# mfl_modul_u6052b.net
KiCad netlist of a schematic drawn in EAGLE
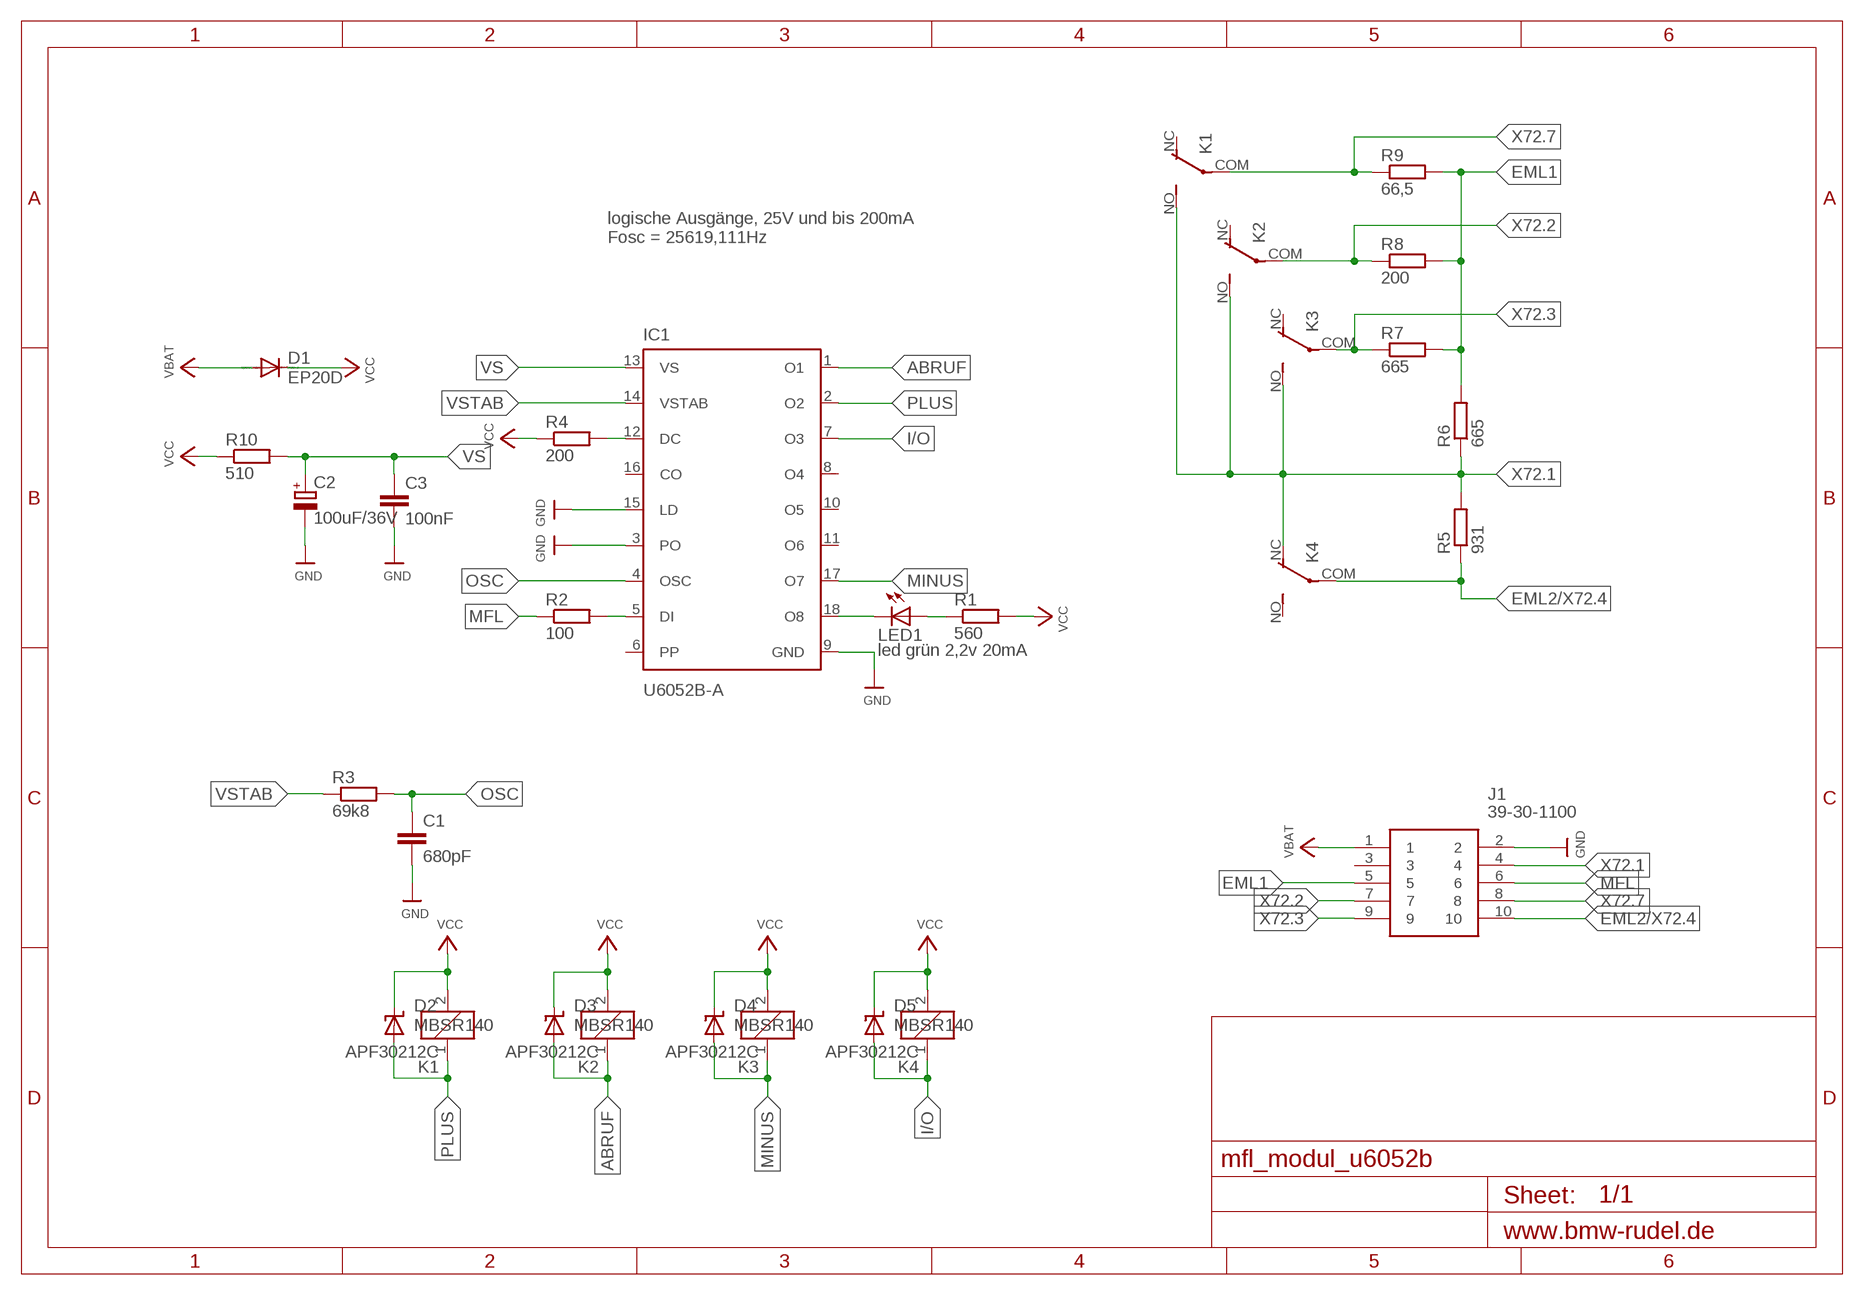
[diagram p0: schematic, sheet 1]

(export (version "E")
  (design (tool "Eeschema 10.0.6"))
  (components
    (comp (ref "C1")
      (value "680pF")
      (footprint "eagle-import:C025-025X050")
      (libsource (lib "eagle-import") (part "C-EU025-025X050"))
    )
    (comp (ref "C2")
      (value "100uF/36V")
      (footprint "eagle-import:E2,5-6")
      (libsource (lib "eagle-import") (part "CPOL-EUE2.5-6"))
    )
    (comp (ref "C3")
      (value "100nF")
      (footprint "eagle-import:C025-025X050")
      (libsource (lib "eagle-import") (part "C-EU025-025X050"))
    )
    (comp (ref "D1")
      (value "EP20D")
      (footprint "eagle-import:DO15-12")
      (libsource (lib "eagle-import") (part "DIODE-DO15-12"))
    )
    (comp (ref "D2")
      (value "MBSR140")
      (footprint "eagle-import:DO214AA")
      (libsource (lib "eagle-import") (part "SHOTKY-SMDSMB"))
    )
    (comp (ref "D3")
      (value "MBSR140")
      (footprint "eagle-import:DO214AA")
      (libsource (lib "eagle-import") (part "SHOTKY-SMDSMB"))
    )
    (comp (ref "D4")
      (value "MBSR140")
      (footprint "eagle-import:DO214AA")
      (libsource (lib "eagle-import") (part "SHOTKY-SMDSMB"))
    )
    (comp (ref "D5")
      (value "MBSR140")
      (footprint "eagle-import:DO214AA")
      (libsource (lib "eagle-import") (part "SHOTKY-SMDSMB"))
    )
    (comp (ref "IC1")
      (value "U6052B-A")
      (footprint "eagle-import:DIL18")
      (libsource (lib "eagle-import") (part "U6052B-A"))
    )
    (comp (ref "J1")
      (value "39-30-1100")
      (footprint "eagle-import:39-30-1100")
      (fields (field (name "MOUSER_PART_NUMBER") "538-39-30-1100") (field (name "RS_PART_NUMBER") "5109871P"))
      (libsource (lib "eagle-import") (part "39-30-1100"))
    )
    (comp (ref "K1")
      (value "APF30212C")
      (footprint "eagle-import:APF30212C")
      (libsource (lib "eagle-import") (part "APF30212C"))
    )
    (comp (ref "K2")
      (value "APF30212C")
      (footprint "eagle-import:APF30212C")
      (libsource (lib "eagle-import") (part "APF30212C"))
    )
    (comp (ref "K3")
      (value "APF30212C")
      (footprint "eagle-import:APF30212C")
      (libsource (lib "eagle-import") (part "APF30212C"))
    )
    (comp (ref "K4")
      (value "APF30212C")
      (footprint "eagle-import:APF30212C")
      (libsource (lib "eagle-import") (part "APF30212C"))
    )
    (comp (ref "LED1")
      (value "led grün 2,2v 20mA")
      (footprint "eagle-import:LED3MM")
      (libsource (lib "eagle-import") (part "LED3MM"))
    )
    (comp (ref "R1")
      (value "560")
      (footprint "eagle-import:0207_7")
      (libsource (lib "eagle-import") (part "R-EU_0207/7"))
    )
    (comp (ref "R2")
      (value "100")
      (footprint "eagle-import:0207_7")
      (libsource (lib "eagle-import") (part "R-EU_0207/7"))
    )
    (comp (ref "R3")
      (value "69k8")
      (footprint "eagle-import:0207_7")
      (libsource (lib "eagle-import") (part "R-EU_0207/7"))
    )
    (comp (ref "R4")
      (value "200")
      (footprint "eagle-import:0207_7")
      (libsource (lib "eagle-import") (part "R-EU_0207/7"))
    )
    (comp (ref "R5")
      (value "931")
      (footprint "eagle-import:0207_7")
      (libsource (lib "eagle-import") (part "R-EU_0207/7"))
    )
    (comp (ref "R6")
      (value "665")
      (footprint "eagle-import:0207_7")
      (libsource (lib "eagle-import") (part "R-EU_0207/7"))
    )
    (comp (ref "R7")
      (value "665")
      (footprint "eagle-import:0207_7")
      (libsource (lib "eagle-import") (part "R-EU_0207/7"))
    )
    (comp (ref "R8")
      (value "200")
      (footprint "eagle-import:0207_7")
      (libsource (lib "eagle-import") (part "R-EU_0207/7"))
    )
    (comp (ref "R9")
      (value "66,5")
      (footprint "eagle-import:0207_7")
      (libsource (lib "eagle-import") (part "R-EU_0207/7"))
    )
    (comp (ref "R10")
      (value "510")
      (footprint "eagle-import:0207_7")
      (libsource (lib "eagle-import") (part "R-EU_0207/7"))
    )
  )
  (nets
    (net (code "1") (name "ABRUF") (class "Default")
      (node (ref "D3") (pin "A") (pinfunction "A_A") (pintype "passive"))
      (node (ref "IC1") (pin "1") (pinfunction "O1_1") (pintype "bidirectional"))
      (node (ref "K2") (pin "1") (pinfunction "1_1") (pintype "passive"))
    )
    (net (code "2") (name "EML1") (class "Default")
      (node (ref "J1") (pin "5") (pinfunction "5_5") (pintype "bidirectional"))
      (node (ref "R6") (pin "2") (pinfunction "2_2") (pintype "passive"))
      (node (ref "R7") (pin "2") (pinfunction "2_2") (pintype "passive"))
      (node (ref "R8") (pin "2") (pinfunction "2_2") (pintype "passive"))
      (node (ref "R9") (pin "2") (pinfunction "2_2") (pintype "passive"))
    )
    (net (code "3") (name "EML2{slash}X72.4") (class "Default")
      (node (ref "J1") (pin "10") (pinfunction "10_10") (pintype "bidirectional"))
      (node (ref "K4") (pin "COM") (pinfunction "P_COM") (pintype "passive"))
      (node (ref "R5") (pin "1") (pinfunction "1_1") (pintype "passive"))
    )
    (net (code "4") (name "GND") (class "Default")
      (node (ref "C1") (pin "2") (pinfunction "2_2") (pintype "passive"))
      (node (ref "C2") (pin "-") (pinfunction "-_-") (pintype "passive"))
      (node (ref "C3") (pin "2") (pinfunction "2_2") (pintype "passive"))
      (node (ref "IC1") (pin "15") (pinfunction "LD_15") (pintype "bidirectional"))
      (node (ref "IC1") (pin "3") (pinfunction "PO_3") (pintype "bidirectional"))
      (node (ref "IC1") (pin "9") (pinfunction "GND_9") (pintype "bidirectional"))
      (node (ref "J1") (pin "2") (pinfunction "2_2") (pintype "bidirectional"))
    )
    (net (code "5") (name "I{slash}O") (class "Default")
      (node (ref "D5") (pin "A") (pinfunction "A_A") (pintype "passive"))
      (node (ref "IC1") (pin "7") (pinfunction "O3_7") (pintype "bidirectional"))
      (node (ref "K4") (pin "1") (pinfunction "1_1") (pintype "passive"))
    )
    (net (code "6") (name "MFL") (class "Default")
      (node (ref "J1") (pin "6") (pinfunction "6_6") (pintype "bidirectional"))
      (node (ref "R2") (pin "1") (pinfunction "1_1") (pintype "passive"))
    )
    (net (code "7") (name "MINUS") (class "Default")
      (node (ref "D4") (pin "A") (pinfunction "A_A") (pintype "passive"))
      (node (ref "IC1") (pin "17") (pinfunction "O7_17") (pintype "bidirectional"))
      (node (ref "K3") (pin "1") (pinfunction "1_1") (pintype "passive"))
    )
    (net (code "8") (name "Net-(IC1-DC)") (class "Default")
      (node (ref "IC1") (pin "12") (pinfunction "DC_12") (pintype "bidirectional"))
      (node (ref "R4") (pin "2") (pinfunction "2_2") (pintype "passive"))
    )
    (net (code "9") (name "Net-(IC1-DI)") (class "Default")
      (node (ref "IC1") (pin "5") (pinfunction "DI_5") (pintype "bidirectional"))
      (node (ref "R2") (pin "2") (pinfunction "2_2") (pintype "passive"))
    )
    (net (code "10") (name "Net-(IC1-O8)") (class "Default")
      (node (ref "IC1") (pin "18") (pinfunction "O8_18") (pintype "bidirectional"))
      (node (ref "LED1") (pin "K") (pinfunction "C_K") (pintype "passive"))
    )
    (net (code "11") (name "Net-(LED1-PadA)") (class "Default")
      (node (ref "LED1") (pin "A") (pinfunction "A_A") (pintype "passive"))
      (node (ref "R1") (pin "1") (pinfunction "1_1") (pintype "passive"))
    )
    (net (code "12") (name "OSC") (class "Default")
      (node (ref "C1") (pin "1") (pinfunction "1_1") (pintype "passive"))
      (node (ref "IC1") (pin "4") (pinfunction "OSC_4") (pintype "bidirectional"))
      (node (ref "R3") (pin "2") (pinfunction "2_2") (pintype "passive"))
    )
    (net (code "13") (name "PLUS") (class "Default")
      (node (ref "D2") (pin "A") (pinfunction "A_A") (pintype "passive"))
      (node (ref "IC1") (pin "2") (pinfunction "O2_2") (pintype "bidirectional"))
      (node (ref "K1") (pin "1") (pinfunction "1_1") (pintype "passive"))
    )
    (net (code "14") (name "VBAT") (class "Default")
      (node (ref "D1") (pin "A") (pinfunction "A_A") (pintype "passive"))
      (node (ref "J1") (pin "1") (pinfunction "1_1") (pintype "bidirectional"))
    )
    (net (code "15") (name "VCC") (class "Default")
      (node (ref "D1") (pin "C") (pinfunction "C_C") (pintype "passive"))
      (node (ref "D2") (pin "C") (pinfunction "C_C") (pintype "passive"))
      (node (ref "D3") (pin "C") (pinfunction "C_C") (pintype "passive"))
      (node (ref "D4") (pin "C") (pinfunction "C_C") (pintype "passive"))
      (node (ref "D5") (pin "C") (pinfunction "C_C") (pintype "passive"))
      (node (ref "K1") (pin "2") (pinfunction "2_2") (pintype "passive"))
      (node (ref "K2") (pin "2") (pinfunction "2_2") (pintype "passive"))
      (node (ref "K3") (pin "2") (pinfunction "2_2") (pintype "passive"))
      (node (ref "K4") (pin "2") (pinfunction "2_2") (pintype "passive"))
      (node (ref "R1") (pin "2") (pinfunction "2_2") (pintype "passive"))
      (node (ref "R10") (pin "1") (pinfunction "1_1") (pintype "passive"))
      (node (ref "R4") (pin "1") (pinfunction "1_1") (pintype "passive"))
    )
    (net (code "16") (name "VS") (class "Default")
      (node (ref "C2") (pin "+") (pinfunction "+_+") (pintype "passive"))
      (node (ref "C3") (pin "1") (pinfunction "1_1") (pintype "passive"))
      (node (ref "IC1") (pin "13") (pinfunction "VS_13") (pintype "bidirectional"))
      (node (ref "R10") (pin "2") (pinfunction "2_2") (pintype "passive"))
    )
    (net (code "17") (name "VSTAB") (class "Default")
      (node (ref "IC1") (pin "14") (pinfunction "VSTAB_14") (pintype "bidirectional"))
      (node (ref "R3") (pin "1") (pinfunction "1_1") (pintype "passive"))
    )
    (net (code "18") (name "X72.1") (class "Default")
      (node (ref "J1") (pin "4") (pinfunction "4_4") (pintype "bidirectional"))
      (node (ref "K1") (pin "NO") (pinfunction "S_NO") (pintype "passive"))
      (node (ref "K2") (pin "NO") (pinfunction "S_NO") (pintype "passive"))
      (node (ref "K3") (pin "NO") (pinfunction "S_NO") (pintype "passive"))
      (node (ref "K4") (pin "NC") (pinfunction "O_NC") (pintype "passive"))
      (node (ref "R5") (pin "2") (pinfunction "2_2") (pintype "passive"))
      (node (ref "R6") (pin "1") (pinfunction "1_1") (pintype "passive"))
    )
    (net (code "19") (name "X72.2") (class "Default")
      (node (ref "J1") (pin "7") (pinfunction "7_7") (pintype "bidirectional"))
      (node (ref "K2") (pin "COM") (pinfunction "P_COM") (pintype "passive"))
      (node (ref "R8") (pin "1") (pinfunction "1_1") (pintype "passive"))
    )
    (net (code "20") (name "X72.3") (class "Default")
      (node (ref "J1") (pin "9") (pinfunction "9_9") (pintype "bidirectional"))
      (node (ref "K3") (pin "COM") (pinfunction "P_COM") (pintype "passive"))
      (node (ref "R7") (pin "1") (pinfunction "1_1") (pintype "passive"))
    )
    (net (code "21") (name "X72.7") (class "Default")
      (node (ref "J1") (pin "8") (pinfunction "8_8") (pintype "bidirectional"))
      (node (ref "K1") (pin "COM") (pinfunction "P_COM") (pintype "passive"))
      (node (ref "R9") (pin "1") (pinfunction "1_1") (pintype "passive"))
    )
    (net (code "22") (name "unconnected-(IC1-CO-Pad16)") (class "Default")
      (node (ref "IC1") (pin "16") (pinfunction "CO_16") (pintype "bidirectional"))
    )
    (net (code "23") (name "unconnected-(IC1-O4-Pad8)") (class "Default")
      (node (ref "IC1") (pin "8") (pinfunction "O4_8") (pintype "bidirectional"))
    )
    (net (code "24") (name "unconnected-(IC1-O5-Pad10)") (class "Default")
      (node (ref "IC1") (pin "10") (pinfunction "O5_10") (pintype "bidirectional"))
    )
    (net (code "25") (name "unconnected-(IC1-O6-Pad11)") (class "Default")
      (node (ref "IC1") (pin "11") (pinfunction "O6_11") (pintype "bidirectional"))
    )
    (net (code "26") (name "unconnected-(IC1-PP-Pad6)") (class "Default")
      (node (ref "IC1") (pin "6") (pinfunction "PP_6") (pintype "bidirectional"))
    )
    (net (code "27") (name "unconnected-(J1-Pad3)") (class "Default")
      (node (ref "J1") (pin "3") (pinfunction "3_3") (pintype "bidirectional"))
    )
    (net (code "28") (name "unconnected-(K1B-O-PadNC)") (class "Default")
      (node (ref "K1") (pin "NC") (pinfunction "O_NC") (pintype "passive"))
    )
    (net (code "29") (name "unconnected-(K2B-O-PadNC)") (class "Default")
      (node (ref "K2") (pin "NC") (pinfunction "O_NC") (pintype "passive"))
    )
    (net (code "30") (name "unconnected-(K3B-O-PadNC)") (class "Default")
      (node (ref "K3") (pin "NC") (pinfunction "O_NC") (pintype "passive"))
    )
    (net (code "31") (name "unconnected-(K4B-S-PadNO)") (class "Default")
      (node (ref "K4") (pin "NO") (pinfunction "S_NO") (pintype "passive"))
    )
  )
)
